# main.net
KiCad netlist of a schematic drawn in Altium Designer
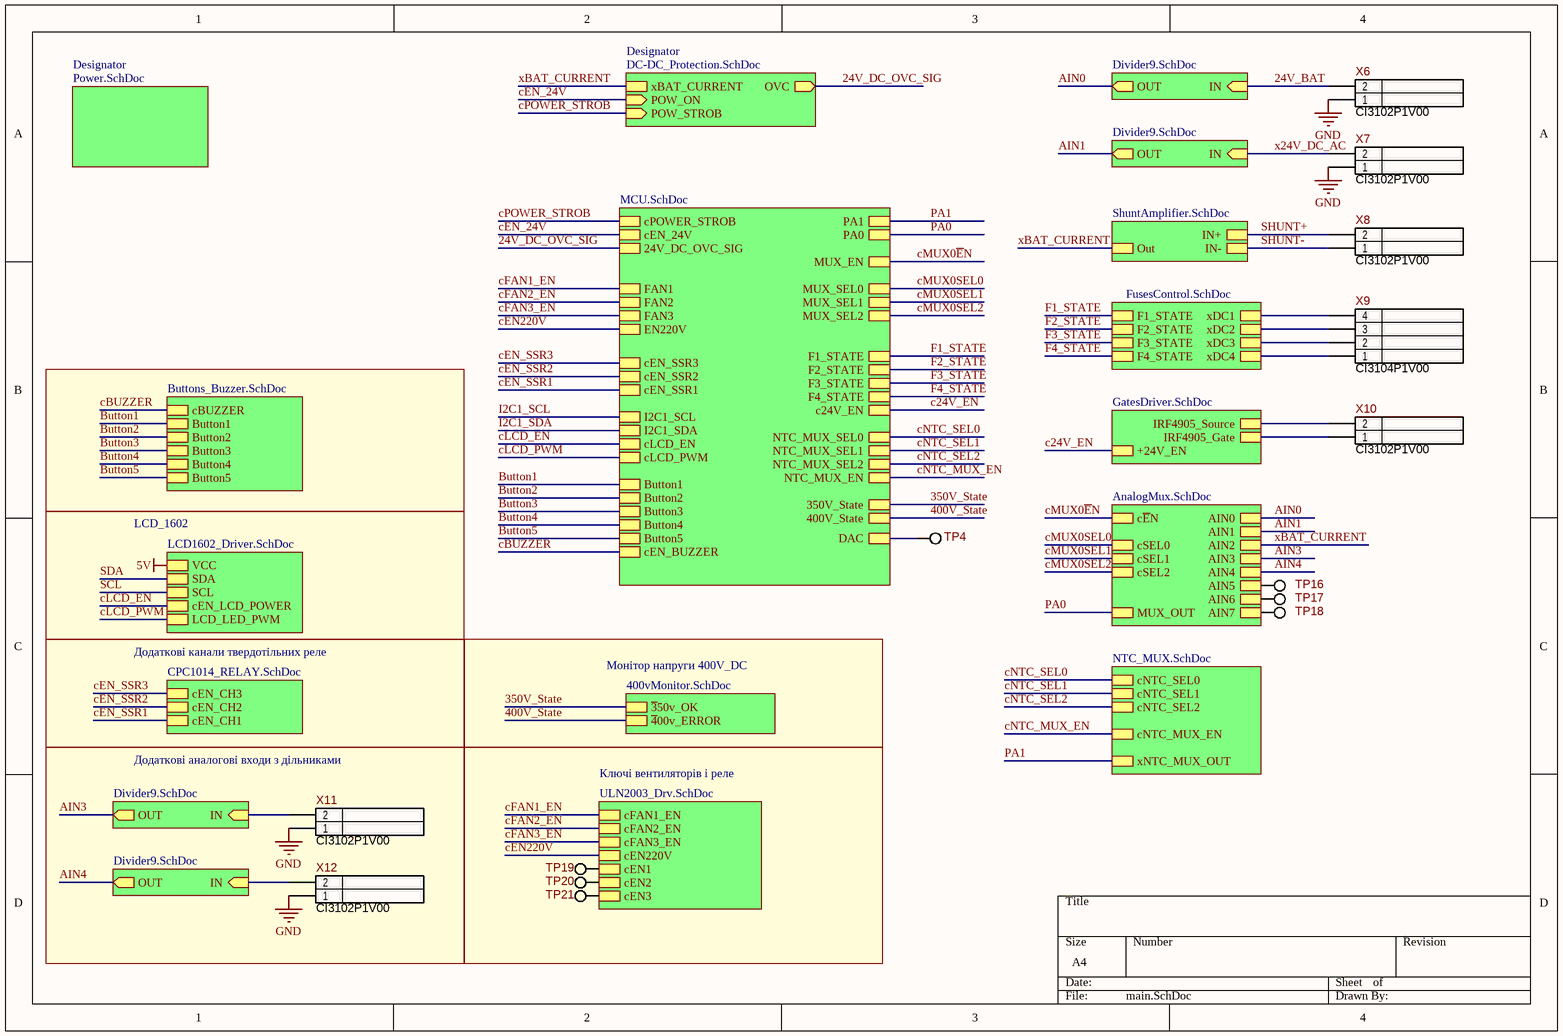
[diagram p0: main.SchDoc]

(export (version "E")
  (design (tool "Eeschema 10.0.6"))
  (components
    (comp (ref "TP4")
      (value "PAD-1.1mm")
      (footprint "PAD-1.1mm")
      (description "1.1mm Pad for Plug-In or Receptacle")
      (fields (field (name "MANUFACTURER") "NONE"))
      (libsource (lib "misc") (part "PAD-1.1mm"))
    )
    (comp (ref "TP16")
      (value "PAD-1.1mm")
      (footprint "PAD-1.1mm")
      (description "1.1mm Pad for Plug-In or Receptacle")
      (fields (field (name "MANUFACTURER") "NONE"))
      (libsource (lib "misc") (part "PAD-1.1mm"))
    )
    (comp (ref "TP17")
      (value "PAD-1.1mm")
      (footprint "PAD-1.1mm")
      (description "1.1mm Pad for Plug-In or Receptacle")
      (fields (field (name "MANUFACTURER") "NONE"))
      (libsource (lib "misc") (part "PAD-1.1mm"))
    )
    (comp (ref "TP18")
      (value "PAD-1.1mm")
      (footprint "PAD-1.1mm")
      (description "1.1mm Pad for Plug-In or Receptacle")
      (fields (field (name "MANUFACTURER") "NONE"))
      (libsource (lib "misc") (part "PAD-1.1mm"))
    )
    (comp (ref "TP19")
      (value "PAD-1.1mm")
      (footprint "PAD-1.1mm")
      (description "1.1mm Pad for Plug-In or Receptacle")
      (fields (field (name "MANUFACTURER") "NONE"))
      (libsource (lib "misc") (part "PAD-1.1mm"))
    )
    (comp (ref "TP20")
      (value "PAD-1.1mm")
      (footprint "PAD-1.1mm")
      (description "1.1mm Pad for Plug-In or Receptacle")
      (fields (field (name "MANUFACTURER") "NONE"))
      (libsource (lib "misc") (part "PAD-1.1mm"))
    )
    (comp (ref "TP21")
      (value "PAD-1.1mm")
      (footprint "PAD-1.1mm")
      (description "1.1mm Pad for Plug-In or Receptacle")
      (fields (field (name "MANUFACTURER") "NONE"))
      (libsource (lib "misc") (part "PAD-1.1mm"))
    )
    (comp (ref "X6")
      (value "WH-02S")
      (footprint "WF-2S")
      (description "WH Series 2.54mm Wire to Board Straight DIP Type Headers, 2-Pin")
      (fields (field (name "PART NUMBER") "CI3102P1V00") (field (name "MANUFACTURER") "CviLux"))
      (libsource (lib "SOG.T01.PWR.621.v1_1") (part "CI3102P1V00"))
    )
    (comp (ref "X7")
      (value "WH-02S")
      (footprint "WF-2S")
      (description "WH Series 2.54mm Wire to Board Straight DIP Type Headers, 2-Pin")
      (fields (field (name "PART NUMBER") "CI3102P1V00") (field (name "MANUFACTURER") "CviLux"))
      (libsource (lib "SOG.T01.PWR.621.v1_1") (part "CI3102P1V00"))
    )
    (comp (ref "X8")
      (value "WH-02S")
      (footprint "WF-2S")
      (description "WH Series 2.54mm Wire to Board Straight DIP Type Headers, 2-Pin")
      (fields (field (name "PART NUMBER") "CI3102P1V00") (field (name "MANUFACTURER") "CviLux"))
      (libsource (lib "SOG.T01.PWR.621.v1_1") (part "CI3102P1V00"))
    )
    (comp (ref "X9")
      (value "WH-04S")
      (footprint "WF-4S")
      (description "WH Series 2.54mm Wire to Board Straight DIP Type Headers, 4 Pin")
      (fields (field (name "PART NUMBER") "CI3104P1V00") (field (name "MANUFACTURER") "CviLux"))
      (libsource (lib "SOG.T01.PWR.621.v1_1") (part "CI3104P1V00"))
    )
    (comp (ref "X10")
      (value "WH-02S")
      (footprint "WF-2S")
      (description "WH Series 2.54mm Wire to Board Straight DIP Type Headers, 2-Pin")
      (fields (field (name "PART NUMBER") "CI3102P1V00") (field (name "MANUFACTURER") "CviLux"))
      (libsource (lib "SOG.T01.PWR.621.v1_1") (part "CI3102P1V00"))
    )
    (comp (ref "X11")
      (value "WH-02S")
      (footprint "WF-2S")
      (description "WH Series 2.54mm Wire to Board Straight DIP Type Headers, 2-Pin")
      (fields (field (name "PART NUMBER") "CI3102P1V00") (field (name "MANUFACTURER") "CviLux"))
      (libsource (lib "SOG.T01.PWR.621.v1_1") (part "CI3102P1V00"))
    )
    (comp (ref "X12")
      (value "WH-02S")
      (footprint "WF-2S")
      (description "WH Series 2.54mm Wire to Board Straight DIP Type Headers, 2-Pin")
      (fields (field (name "PART NUMBER") "CI3102P1V00") (field (name "MANUFACTURER") "CviLux"))
      (libsource (lib "SOG.T01.PWR.621.v1_1") (part "CI3102P1V00"))
    )
  )
  (nets
    (net (code "1") (name "/24V_BAT") (class "Default")
      (node (ref "X6") (pin "2") (pinfunction "2_2") (pintype "passive"))
    )
    (net (code "9") (name "/AIN5") (class "Default") (node (ref "TP16") (pin "1") (pintype "passive")))
    (net (code "10") (name "/AIN6") (class "Default") (node (ref "TP17") (pin "1") (pintype "passive")))
    (net (code "11") (name "/AIN7") (class "Default") (node (ref "TP18") (pin "1") (pintype "passive")))
    (net (code "17") (name "/DAC") (class "Default") (node (ref "TP4") (pin "1") (pintype "passive")))
    (net (code "24") (name "/IN") (class "Default")
      (node (ref "X12") (pin "2") (pinfunction "2_2") (pintype "passive"))
    )
    (net (code "25") (name "/IN_1") (class "Default")
      (node (ref "X11") (pin "2") (pinfunction "2_2") (pintype "passive"))
    )
    (net (code "26") (name "/IRF4905_Gate") (class "Default")
      (node (ref "X10") (pin "1") (pinfunction "1_1") (pintype "passive"))
    )
    (net (code "27") (name "/IRF4905_Source") (class "Default")
      (node (ref "X10") (pin "2") (pinfunction "2_2") (pintype "passive"))
    )
    (net (code "32") (name "/SHUNT+") (class "Default")
      (node (ref "X8") (pin "2") (pinfunction "2_2") (pintype "passive"))
    )
    (net (code "33") (name "/SHUNT-") (class "Default")
      (node (ref "X8") (pin "1") (pinfunction "1_1") (pintype "passive"))
    )
    (net (code "36") (name "/cEN1") (class "Default") (node (ref "TP19") (pin "1") (pintype "passive")))
    (net (code "37") (name "/cEN2") (class "Default") (node (ref "TP20") (pin "1") (pintype "passive")))
    (net (code "38") (name "/cEN3") (class "Default") (node (ref "TP21") (pin "1") (pintype "passive")))
    (net (code "58") (name "/x24V_DC_AC") (class "Default")
      (node (ref "X7") (pin "2") (pinfunction "2_2") (pintype "passive"))
    )
    (net (code "60") (name "/xDC1") (class "Default")
      (node (ref "X9") (pin "4") (pinfunction "4_4") (pintype "passive"))
    )
    (net (code "61") (name "/xDC2") (class "Default")
      (node (ref "X9") (pin "3") (pinfunction "3_3") (pintype "passive"))
    )
    (net (code "62") (name "/xDC3") (class "Default")
      (node (ref "X9") (pin "2") (pinfunction "2_2") (pintype "passive"))
    )
    (net (code "63") (name "/xDC4") (class "Default")
      (node (ref "X9") (pin "1") (pinfunction "1_1") (pintype "passive"))
    )
    (net (code "65") (name "GND") (class "Default")
      (node (ref "X11") (pin "1") (pinfunction "1_1") (pintype "passive"))
      (node (ref "X12") (pin "1") (pinfunction "1_1") (pintype "passive"))
      (node (ref "X6") (pin "1") (pinfunction "1_1") (pintype "passive"))
      (node (ref "X7") (pin "1") (pinfunction "1_1") (pintype "passive"))
    )
  )
)
